# EVmulator_T10_Compact.net
KiCad netlist of a schematic drawn in EAGLE
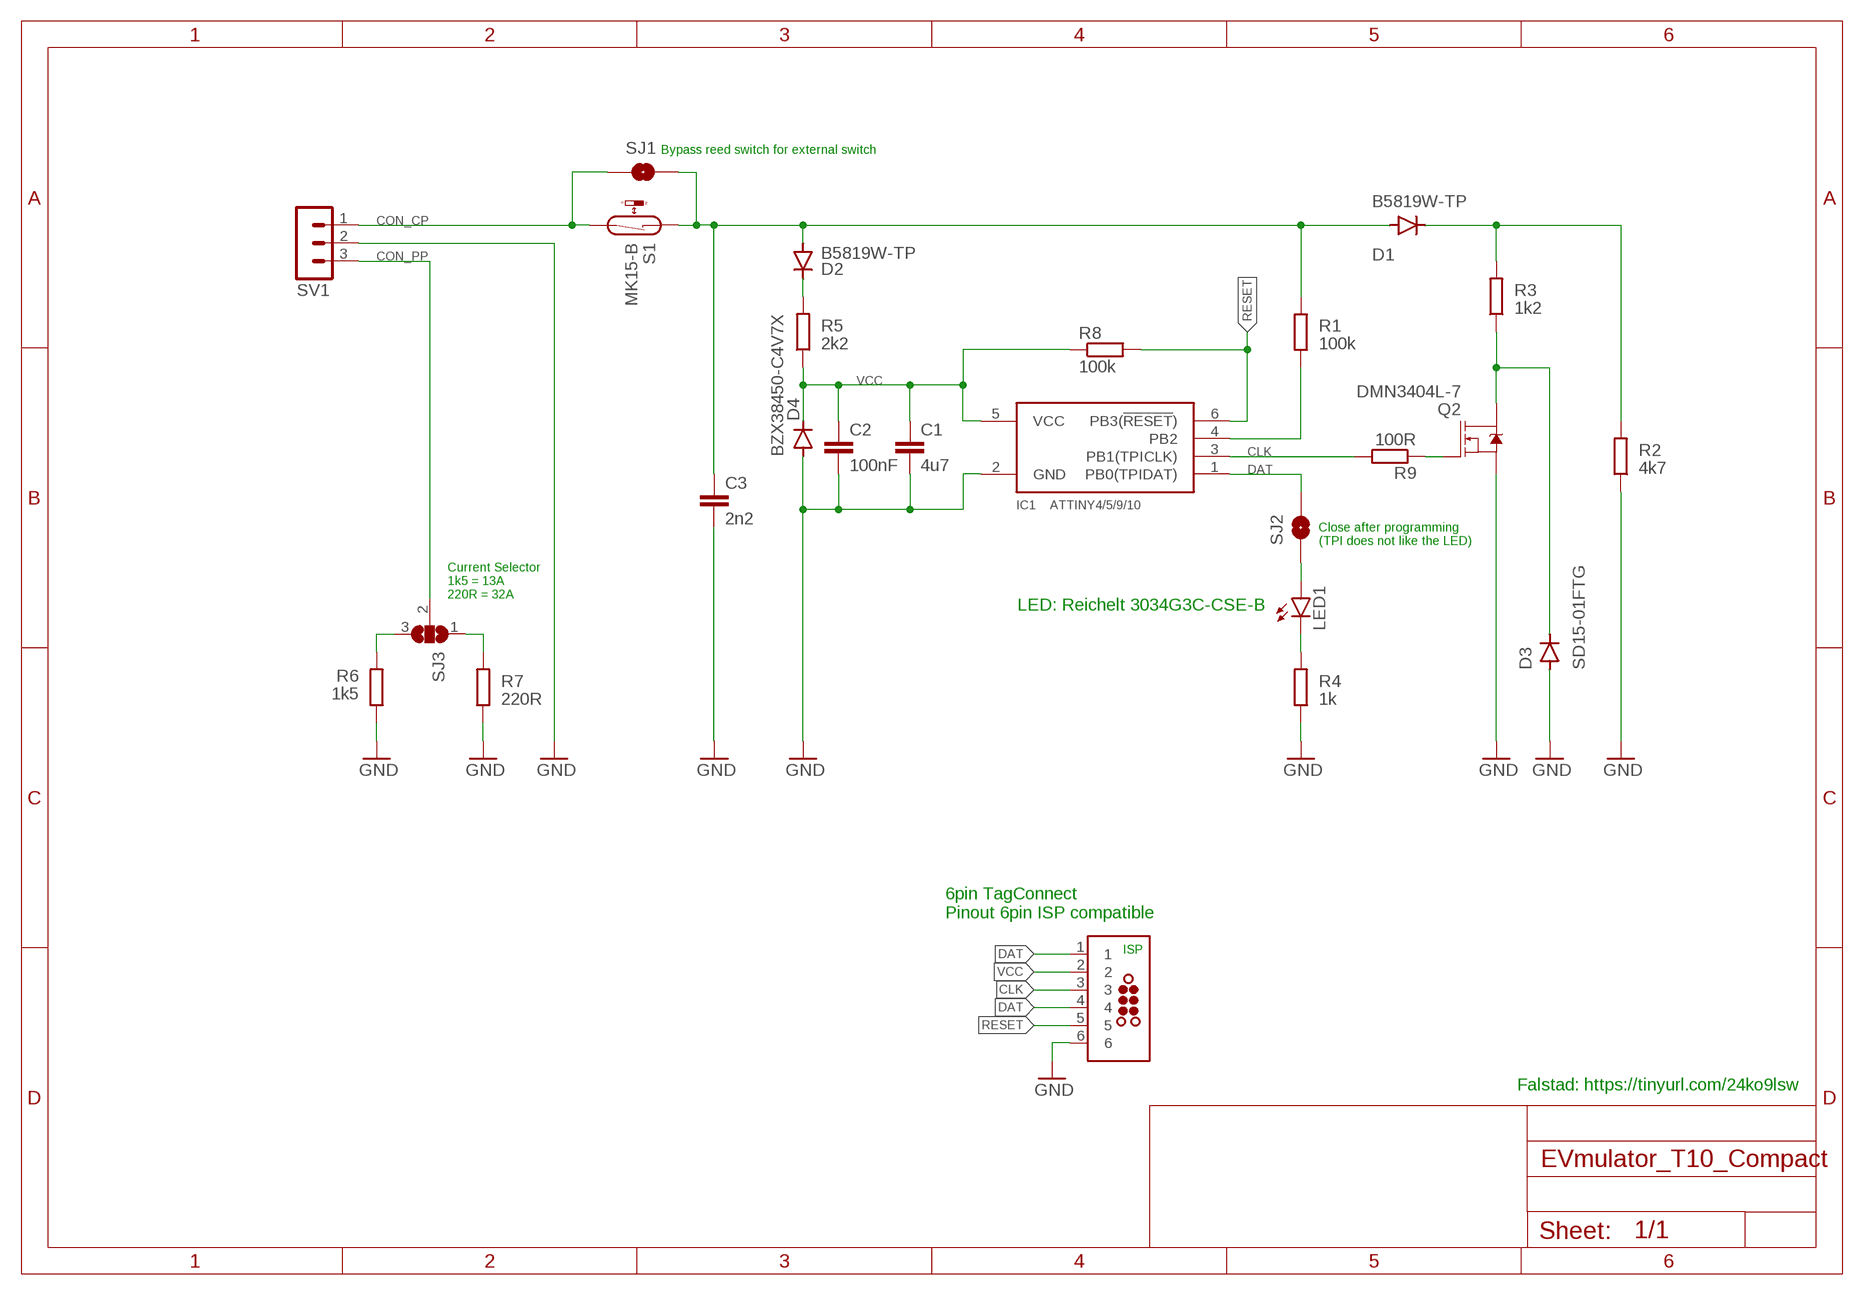
[diagram p0: schematic, sheet 1]

(export (version "E")
  (design (tool "Eeschema 10.0.6"))
  (components
    (comp (ref "C1")
      (value "4u7")
      (footprint "eagle-import:C0603")
      (libsource (lib "eagle-import") (part "C-EUC0603"))
    )
    (comp (ref "C2")
      (value "100nF")
      (footprint "eagle-import:C0603")
      (libsource (lib "eagle-import") (part "C-EUC0603"))
    )
    (comp (ref "C3")
      (value "2n2")
      (footprint "eagle-import:C0603")
      (libsource (lib "eagle-import") (part "C-EUC0603"))
    )
    (comp (ref "D1")
      (value "B5819W-TP")
      (footprint "eagle-import:SOD123")
      (libsource (lib "eagle-import") (part "DIODE-SOD123"))
    )
    (comp (ref "D2")
      (value "B5819W-TP")
      (footprint "eagle-import:SOD123")
      (libsource (lib "eagle-import") (part "DIODE-SOD123"))
    )
    (comp (ref "D3")
      (value "SD15-01FTG")
      (footprint "eagle-import:SOD323-W")
      (libsource (lib "eagle-import") (part "DIODE-SOD323-W"))
    )
    (comp (ref "D4")
      (value "BZX38450-C4V7X")
      (footprint "eagle-import:SOD323-W")
      (libsource (lib "eagle-import") (part "DIODE-SOD323-W"))
    )
    (comp (ref "IC1")
      (value "ATTINY4/5/9/10")
      (footprint "eagle-import:SOT23-6")
      (libsource (lib "eagle-import") (part "ATTINY4/5/9/10"))
    )
    (comp (ref "J1")
      (value "TAG-CONNECT_TC2030-MCP-NL")
      (footprint "eagle-import:TAG-CONNECT_TC2030-MCP-NL")
      (libsource (lib "eagle-import") (part "TAG-CONNECT_TC2030-MCP-NL"))
    )
    (comp (ref "LED1")
      (value "LED3MM")
      (footprint "eagle-import:LED3MM")
      (libsource (lib "eagle-import") (part "LED3MM"))
    )
    (comp (ref "Q2")
      (value "DMN3404L-7")
      (footprint "eagle-import:SOT23-3")
      (libsource (lib "eagle-import") (part "MOSFET-NCH-AO3404A"))
    )
    (comp (ref "R1")
      (value "100k")
      (footprint "eagle-import:R0603")
      (libsource (lib "eagle-import") (part "R-EU_R0603"))
    )
    (comp (ref "R2")
      (value "4k7")
      (footprint "eagle-import:R0603")
      (libsource (lib "eagle-import") (part "R-EU_R0603"))
    )
    (comp (ref "R3")
      (value "1k2")
      (footprint "eagle-import:R0603")
      (libsource (lib "eagle-import") (part "R-EU_R0603"))
    )
    (comp (ref "R4")
      (value "1k")
      (footprint "eagle-import:R0603")
      (libsource (lib "eagle-import") (part "R-EU_R0603"))
    )
    (comp (ref "R5")
      (value "2k2")
      (footprint "eagle-import:R0603")
      (libsource (lib "eagle-import") (part "R-EU_R0603"))
    )
    (comp (ref "R6")
      (value "1k5")
      (footprint "eagle-import:R0805")
      (libsource (lib "eagle-import") (part "R-EU_R0805"))
    )
    (comp (ref "R7")
      (value "220R")
      (footprint "eagle-import:R0805")
      (libsource (lib "eagle-import") (part "R-EU_R0805"))
    )
    (comp (ref "R8")
      (value "100k")
      (footprint "eagle-import:R0603")
      (libsource (lib "eagle-import") (part "R-EU_R0603"))
    )
    (comp (ref "R9")
      (value "100R")
      (footprint "eagle-import:R0603")
      (libsource (lib "eagle-import") (part "R-EU_R0603"))
    )
    (comp (ref "S1")
      (value "MK15-B")
      (footprint "eagle-import:MK15")
      (fields (field (name "MF") "MEDER") (field (name "MPN") "MK15-B-2"))
      (libsource (lib "eagle-import") (part "REED-SWITCH-MK15-B"))
    )
    (comp (ref "SJ1")
      (value "JUMPER-SMT_2_NO_SILK")
      (footprint "eagle-import:SMT-JUMPER_2_NO_SILK")
      (libsource (lib "eagle-import") (part "JUMPER-SMT_2_NO_SILK"))
    )
    (comp (ref "SJ2")
      (value "JUMPER-SMT_2_NO_SILK")
      (footprint "eagle-import:SMT-JUMPER_2_NO_SILK")
      (libsource (lib "eagle-import") (part "JUMPER-SMT_2_NO_SILK"))
    )
    (comp (ref "SJ3")
      (value "SJ2W")
      (footprint "eagle-import:SJ_2")
      (libsource (lib "eagle-import") (part "SJ2W"))
    )
    (comp (ref "SV1")
      (value "MA03-1")
      (footprint "eagle-import:MA03-1")
      (libsource (lib "eagle-import") (part "MA03-1"))
    )
  )
  (nets
    (net (code "1") (name "/CON_CP") (class "Default")
      (node (ref "S1") (pin "2") (pinfunction "2_2") (pintype "passive"))
      (node (ref "SJ1") (pin "1") (pinfunction "1_1") (pintype "passive"))
      (node (ref "SV1") (pin "1") (pinfunction "1_1") (pintype "passive"))
    )
    (net (code "2") (name "/CON_PP") (class "Default")
      (node (ref "SJ3") (pin "2") (pinfunction "2_2") (pintype "passive"))
      (node (ref "SV1") (pin "3") (pinfunction "3_3") (pintype "passive"))
    )
    (net (code "3") (name "CLK") (class "Default")
      (node (ref "IC1") (pin "3") (pinfunction "PB1(TPICLK)_3") (pintype "bidirectional"))
      (node (ref "J1") (pin "3") (pinfunction "3_3") (pintype "power_in"))
      (node (ref "R9") (pin "2") (pinfunction "2_2") (pintype "passive"))
    )
    (net (code "4") (name "DAT") (class "Default")
      (node (ref "IC1") (pin "1") (pinfunction "PB0(TPIDAT)_1") (pintype "bidirectional"))
      (node (ref "J1") (pin "1") (pinfunction "1_1") (pintype "passive"))
      (node (ref "J1") (pin "4") (pinfunction "4_4") (pintype "bidirectional"))
      (node (ref "SJ2") (pin "2") (pinfunction "2_2") (pintype "passive"))
    )
    (net (code "5") (name "GND") (class "Default")
      (node (ref "C1") (pin "2") (pinfunction "2_2") (pintype "passive"))
      (node (ref "C2") (pin "2") (pinfunction "2_2") (pintype "passive"))
      (node (ref "C3") (pin "2") (pinfunction "2_2") (pintype "passive"))
      (node (ref "D3") (pin "A") (pinfunction "A_A") (pintype "passive"))
      (node (ref "D4") (pin "A") (pinfunction "A_A") (pintype "passive"))
      (node (ref "IC1") (pin "2") (pinfunction "GND_2") (pintype "bidirectional"))
      (node (ref "J1") (pin "6") (pinfunction "6_6") (pintype "bidirectional"))
      (node (ref "Q2") (pin "2") (pinfunction "S_2") (pintype "bidirectional"))
      (node (ref "R2") (pin "1") (pinfunction "1_1") (pintype "passive"))
      (node (ref "R4") (pin "1") (pinfunction "1_1") (pintype "passive"))
      (node (ref "R6") (pin "1") (pinfunction "1_1") (pintype "passive"))
      (node (ref "R7") (pin "1") (pinfunction "1_1") (pintype "passive"))
      (node (ref "SV1") (pin "2") (pinfunction "2_2") (pintype "passive"))
    )
    (net (code "6") (name "Net-(C3-Pad1)") (class "Default")
      (node (ref "C3") (pin "1") (pinfunction "1_1") (pintype "passive"))
      (node (ref "D1") (pin "A") (pinfunction "A_A") (pintype "passive"))
      (node (ref "D2") (pin "A") (pinfunction "A_A") (pintype "passive"))
      (node (ref "R1") (pin "1") (pinfunction "1_1") (pintype "passive"))
      (node (ref "S1") (pin "1") (pinfunction "1_1") (pintype "passive"))
      (node (ref "SJ1") (pin "2") (pinfunction "2_2") (pintype "passive"))
    )
    (net (code "7") (name "Net-(D1-PadC)") (class "Default")
      (node (ref "D1") (pin "C") (pinfunction "C_C") (pintype "passive"))
      (node (ref "R2") (pin "2") (pinfunction "2_2") (pintype "passive"))
      (node (ref "R3") (pin "2") (pinfunction "2_2") (pintype "passive"))
    )
    (net (code "8") (name "Net-(D2-PadC)") (class "Default")
      (node (ref "D2") (pin "C") (pinfunction "C_C") (pintype "passive"))
      (node (ref "R5") (pin "2") (pinfunction "2_2") (pintype "passive"))
    )
    (net (code "9") (name "Net-(IC1-PB2)") (class "Default")
      (node (ref "IC1") (pin "4") (pinfunction "PB2_4") (pintype "bidirectional"))
      (node (ref "R1") (pin "2") (pinfunction "2_2") (pintype "passive"))
    )
    (net (code "10") (name "Net-(LED1-C)") (class "Default")
      (node (ref "LED1") (pin "K") (pinfunction "C_K") (pintype "passive"))
      (node (ref "R4") (pin "2") (pinfunction "2_2") (pintype "passive"))
    )
    (net (code "11") (name "Net-(LED1-PadA)") (class "Default")
      (node (ref "LED1") (pin "A") (pinfunction "A_A") (pintype "passive"))
      (node (ref "SJ2") (pin "1") (pinfunction "1_1") (pintype "passive"))
    )
    (net (code "12") (name "Net-(Q2-D)") (class "Default")
      (node (ref "D3") (pin "C") (pinfunction "C_C") (pintype "passive"))
      (node (ref "Q2") (pin "3") (pinfunction "D_3") (pintype "bidirectional"))
      (node (ref "R3") (pin "1") (pinfunction "1_1") (pintype "passive"))
    )
    (net (code "13") (name "Net-(Q2-G)") (class "Default")
      (node (ref "Q2") (pin "1") (pinfunction "G_1") (pintype "bidirectional"))
      (node (ref "R9") (pin "1") (pinfunction "1_1") (pintype "passive"))
    )
    (net (code "14") (name "Net-(R6-Pad2)") (class "Default")
      (node (ref "R6") (pin "2") (pinfunction "2_2") (pintype "passive"))
      (node (ref "SJ3") (pin "3") (pinfunction "3_3") (pintype "passive"))
    )
    (net (code "15") (name "Net-(R7-Pad2)") (class "Default")
      (node (ref "R7") (pin "2") (pinfunction "2_2") (pintype "passive"))
      (node (ref "SJ3") (pin "1") (pinfunction "1_1") (pintype "passive"))
    )
    (net (code "16") (name "RESET") (class "Default")
      (node (ref "IC1") (pin "6") (pinfunction "PB3(~{RESET})_6") (pintype "bidirectional"))
      (node (ref "J1") (pin "5") (pinfunction "5_5") (pintype "output"))
      (node (ref "R8") (pin "2") (pinfunction "2_2") (pintype "passive"))
    )
    (net (code "17") (name "VCC") (class "Default")
      (node (ref "C1") (pin "1") (pinfunction "1_1") (pintype "passive"))
      (node (ref "C2") (pin "1") (pinfunction "1_1") (pintype "passive"))
      (node (ref "D4") (pin "C") (pinfunction "C_C") (pintype "passive"))
      (node (ref "IC1") (pin "5") (pinfunction "VCC_5") (pintype "bidirectional"))
      (node (ref "J1") (pin "2") (pinfunction "2_2") (pintype "power_in"))
      (node (ref "R5") (pin "1") (pinfunction "1_1") (pintype "passive"))
      (node (ref "R8") (pin "1") (pinfunction "1_1") (pintype "passive"))
    )
  )
)
